# AD603_MCP41010.net
KiCad netlist of a schematic drawn in Altium Designer
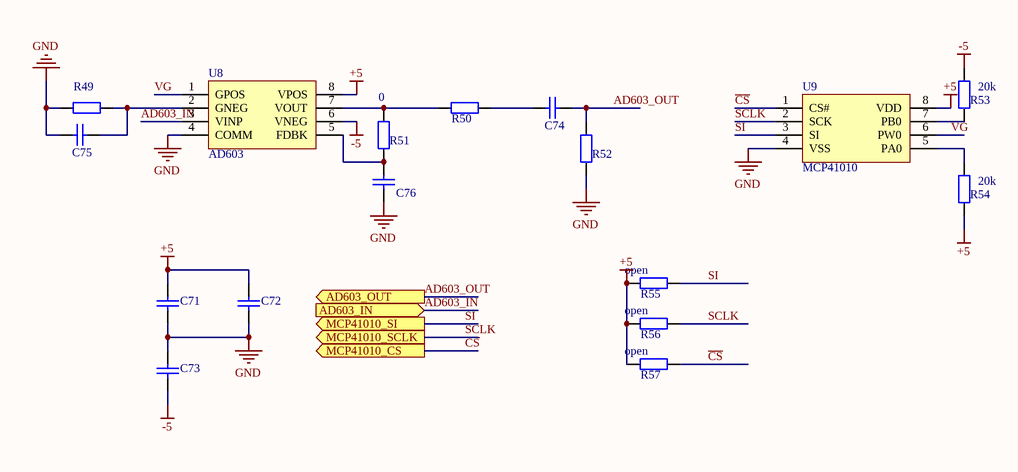
[diagram p0: AD603_MCP41010.SchDoc]

(export (version "E")
  (design (tool "Eeschema 10.0.6"))
  (components
    (comp (ref "C71")
      (value "100nF (104) 10% 50V")
      (footprint "0603_C")
      (description "贴片电容")
      (libsource (lib "JLC") (part "0603 100nF (104) 10% 50V"))
    )
    (comp (ref "C72")
      (value "100nF (104) 10% 50V")
      (footprint "0603_C")
      (description "贴片电容")
      (libsource (lib "JLC") (part "0603 100nF (104) 10% 50V"))
    )
    (comp (ref "C73")
      (value "100nF (104) 10% 50V")
      (footprint "0603_C")
      (description "贴片电容")
      (libsource (lib "JLC") (part "0603 100nF (104) 10% 50V"))
    )
    (comp (ref "C74")
      (value "100nF (104) 10% 50V")
      (footprint "0603_C")
      (description "贴片电容")
      (libsource (lib "JLC") (part "0603 100nF (104) 10% 50V"))
    )
    (comp (ref "C75")
      (value "100nF (104) 10% 50V")
      (footprint "0603_C")
      (description "贴片电容")
      (libsource (lib "JLC") (part "0603 100nF (104) 10% 50V"))
    )
    (comp (ref "C76")
      (value "10pf")
      (footprint "0603_C")
      (description "贴片电容")
      (libsource (lib "JLC") (part "0603 100nF (104) 10% 50V"))
    )
    (comp (ref "R49")
      (value "10KΩ (1002) ±1%")
      (footprint "0603_R")
      (description "贴片电阻")
      (libsource (lib "") (part "0603 10KΩ (1002) 1%_2"))
    )
    (comp (ref "R50")
      (value "10KΩ (1002) ±1%")
      (footprint "0603_R")
      (description "贴片电阻")
      (libsource (lib "JLC") (part "0603 10KΩ (1002) 1%"))
    )
    (comp (ref "R51")
      (value "0")
      (footprint "0603_R")
      (description "贴片电阻")
      (libsource (lib "") (part "0603 10KΩ (1002) 1%_1"))
    )
    (comp (ref "R52")
      (value "10KΩ (1002) ±1%")
      (footprint "0603_R")
      (description "贴片电阻")
      (libsource (lib "") (part "0603 10KΩ (1002) 1%_3"))
    )
    (comp (ref "R53")
      (value "20k")
      (footprint "0603_R")
      (description "贴片电阻")
      (libsource (lib "") (part "0603 10KΩ (1002) 1%_1"))
    )
    (comp (ref "R54")
      (value "20k")
      (footprint "0603_R")
      (description "贴片电阻")
      (libsource (lib "") (part "0603 10KΩ (1002) 1%_1"))
    )
    (comp (ref "R55")
      (value "open")
      (footprint "0603_R")
      (description "贴片电阻")
      (libsource (lib "JLC") (part "0603 10KΩ (1002) 1%"))
    )
    (comp (ref "R56")
      (value "open")
      (footprint "0603_R")
      (description "贴片电阻")
      (libsource (lib "JLC") (part "0603 10KΩ (1002) 1%"))
    )
    (comp (ref "R57")
      (value "open")
      (footprint "0603_R")
      (description "贴片电阻")
      (libsource (lib "JLC") (part "0603 10KΩ (1002) 1%"))
    )
    (comp (ref "U8") (value "AD603") (footprint "SO-8") (libsource (lib "Cooperation") (part "AD603")))
    (comp (ref "U9")
      (value "MCP41010")
      (footprint "SOIC-8")
      (libsource (lib "Cooperation") (part "IC_MCP41010T"))
    )
  )
  (nets
    (net (code "1") (name "+5") (class "Default")
      (node (ref "C71") (pin "2") (pinfunction "2_2") (pintype "passive"))
      (node (ref "C72") (pin "2") (pinfunction "2_2") (pintype "passive"))
      (node (ref "R54") (pin "2") (pinfunction "2_2") (pintype "passive"))
      (node (ref "R55") (pin "1") (pinfunction "1_1") (pintype "passive"))
      (node (ref "R56") (pin "1") (pinfunction "1_1") (pintype "passive"))
      (node (ref "R57") (pin "1") (pinfunction "1_1") (pintype "passive"))
      (node (ref "U8") (pin "8") (pinfunction "VPOS_8") (pintype "passive"))
      (node (ref "U9") (pin "8") (pinfunction "VDD_8") (pintype "passive"))
    )
    (net (code "2") (name "-5") (class "Default")
      (node (ref "C73") (pin "1") (pinfunction "1_1") (pintype "passive"))
      (node (ref "R53") (pin "1") (pinfunction "1_1") (pintype "passive"))
      (node (ref "U8") (pin "6") (pinfunction "VNEG_6") (pintype "passive"))
    )
    (net (code "3") (name "/AD603_IN") (class "Default")
      (node (ref "U8") (pin "3") (pinfunction "VINP_3") (pintype "passive"))
    )
    (net (code "4") (name "/AD603_OUT") (class "Default")
      (node (ref "C74") (pin "1") (pinfunction "1_1") (pintype "passive"))
      (node (ref "R52") (pin "2") (pinfunction "2_2") (pintype "passive"))
    )
    (net (code "5") (name "/SCLK") (class "Default")
      (node (ref "R56") (pin "2") (pinfunction "2_2") (pintype "passive"))
      (node (ref "U9") (pin "2") (pinfunction "SCK_2") (pintype "passive"))
    )
    (net (code "6") (name "/SI") (class "Default")
      (node (ref "R55") (pin "2") (pinfunction "2_2") (pintype "passive"))
      (node (ref "U9") (pin "3") (pinfunction "SI_3") (pintype "passive"))
    )
    (net (code "7") (name "/VG") (class "Default")
      (node (ref "U8") (pin "1") (pinfunction "GPOS_1") (pintype "passive"))
      (node (ref "U9") (pin "6") (pinfunction "PW0_6") (pintype "passive"))
    )
    (net (code "8") (name "/~{CS}") (class "Default")
      (node (ref "R57") (pin "2") (pinfunction "2_2") (pintype "passive"))
      (node (ref "U9") (pin "1") (pinfunction "CS#_1") (pintype "passive"))
    )
    (net (code "9") (name "GND") (class "Default")
      (node (ref "C71") (pin "1") (pinfunction "1_1") (pintype "passive"))
      (node (ref "C72") (pin "1") (pinfunction "1_1") (pintype "passive"))
      (node (ref "C73") (pin "2") (pinfunction "2_2") (pintype "passive"))
      (node (ref "C75") (pin "2") (pinfunction "2_2") (pintype "passive"))
      (node (ref "C76") (pin "2") (pinfunction "2_2") (pintype "passive"))
      (node (ref "R49") (pin "2") (pinfunction "2_2") (pintype "passive"))
      (node (ref "R52") (pin "1") (pinfunction "1_1") (pintype "passive"))
      (node (ref "U8") (pin "4") (pinfunction "COMM_4") (pintype "passive"))
      (node (ref "U9") (pin "4") (pinfunction "VSS_4") (pintype "passive"))
    )
    (net (code "10") (name "Net-(C74-Pad2)") (class "Default")
      (node (ref "C74") (pin "2") (pinfunction "2_2") (pintype "passive"))
      (node (ref "R50") (pin "2") (pinfunction "2_2") (pintype "passive"))
    )
    (net (code "11") (name "Net-(U8-FDBK)") (class "Default")
      (node (ref "C76") (pin "1") (pinfunction "1_1") (pintype "passive"))
      (node (ref "R51") (pin "2") (pinfunction "2_2") (pintype "passive"))
      (node (ref "U8") (pin "5") (pinfunction "FDBK_5") (pintype "passive"))
    )
    (net (code "12") (name "Net-(U8-GNEG)") (class "Default")
      (node (ref "C75") (pin "1") (pinfunction "1_1") (pintype "passive"))
      (node (ref "R49") (pin "1") (pinfunction "1_1") (pintype "passive"))
      (node (ref "U8") (pin "2") (pinfunction "GNEG_2") (pintype "passive"))
    )
    (net (code "13") (name "Net-(U8-VOUT)") (class "Default")
      (node (ref "R50") (pin "1") (pinfunction "1_1") (pintype "passive"))
      (node (ref "R51") (pin "1") (pinfunction "1_1") (pintype "passive"))
      (node (ref "U8") (pin "7") (pinfunction "VOUT_7") (pintype "passive"))
    )
    (net (code "14") (name "Net-(U9-PA0)") (class "Default")
      (node (ref "R54") (pin "1") (pinfunction "1_1") (pintype "passive"))
      (node (ref "U9") (pin "5") (pinfunction "PA0_5") (pintype "passive"))
    )
    (net (code "15") (name "Net-(U9-PB0)") (class "Default")
      (node (ref "R53") (pin "2") (pinfunction "2_2") (pintype "passive"))
      (node (ref "U9") (pin "7") (pinfunction "PB0_7") (pintype "passive"))
    )
  )
)
